# ap.net
KiCad netlist of a schematic drawn in EAGLE
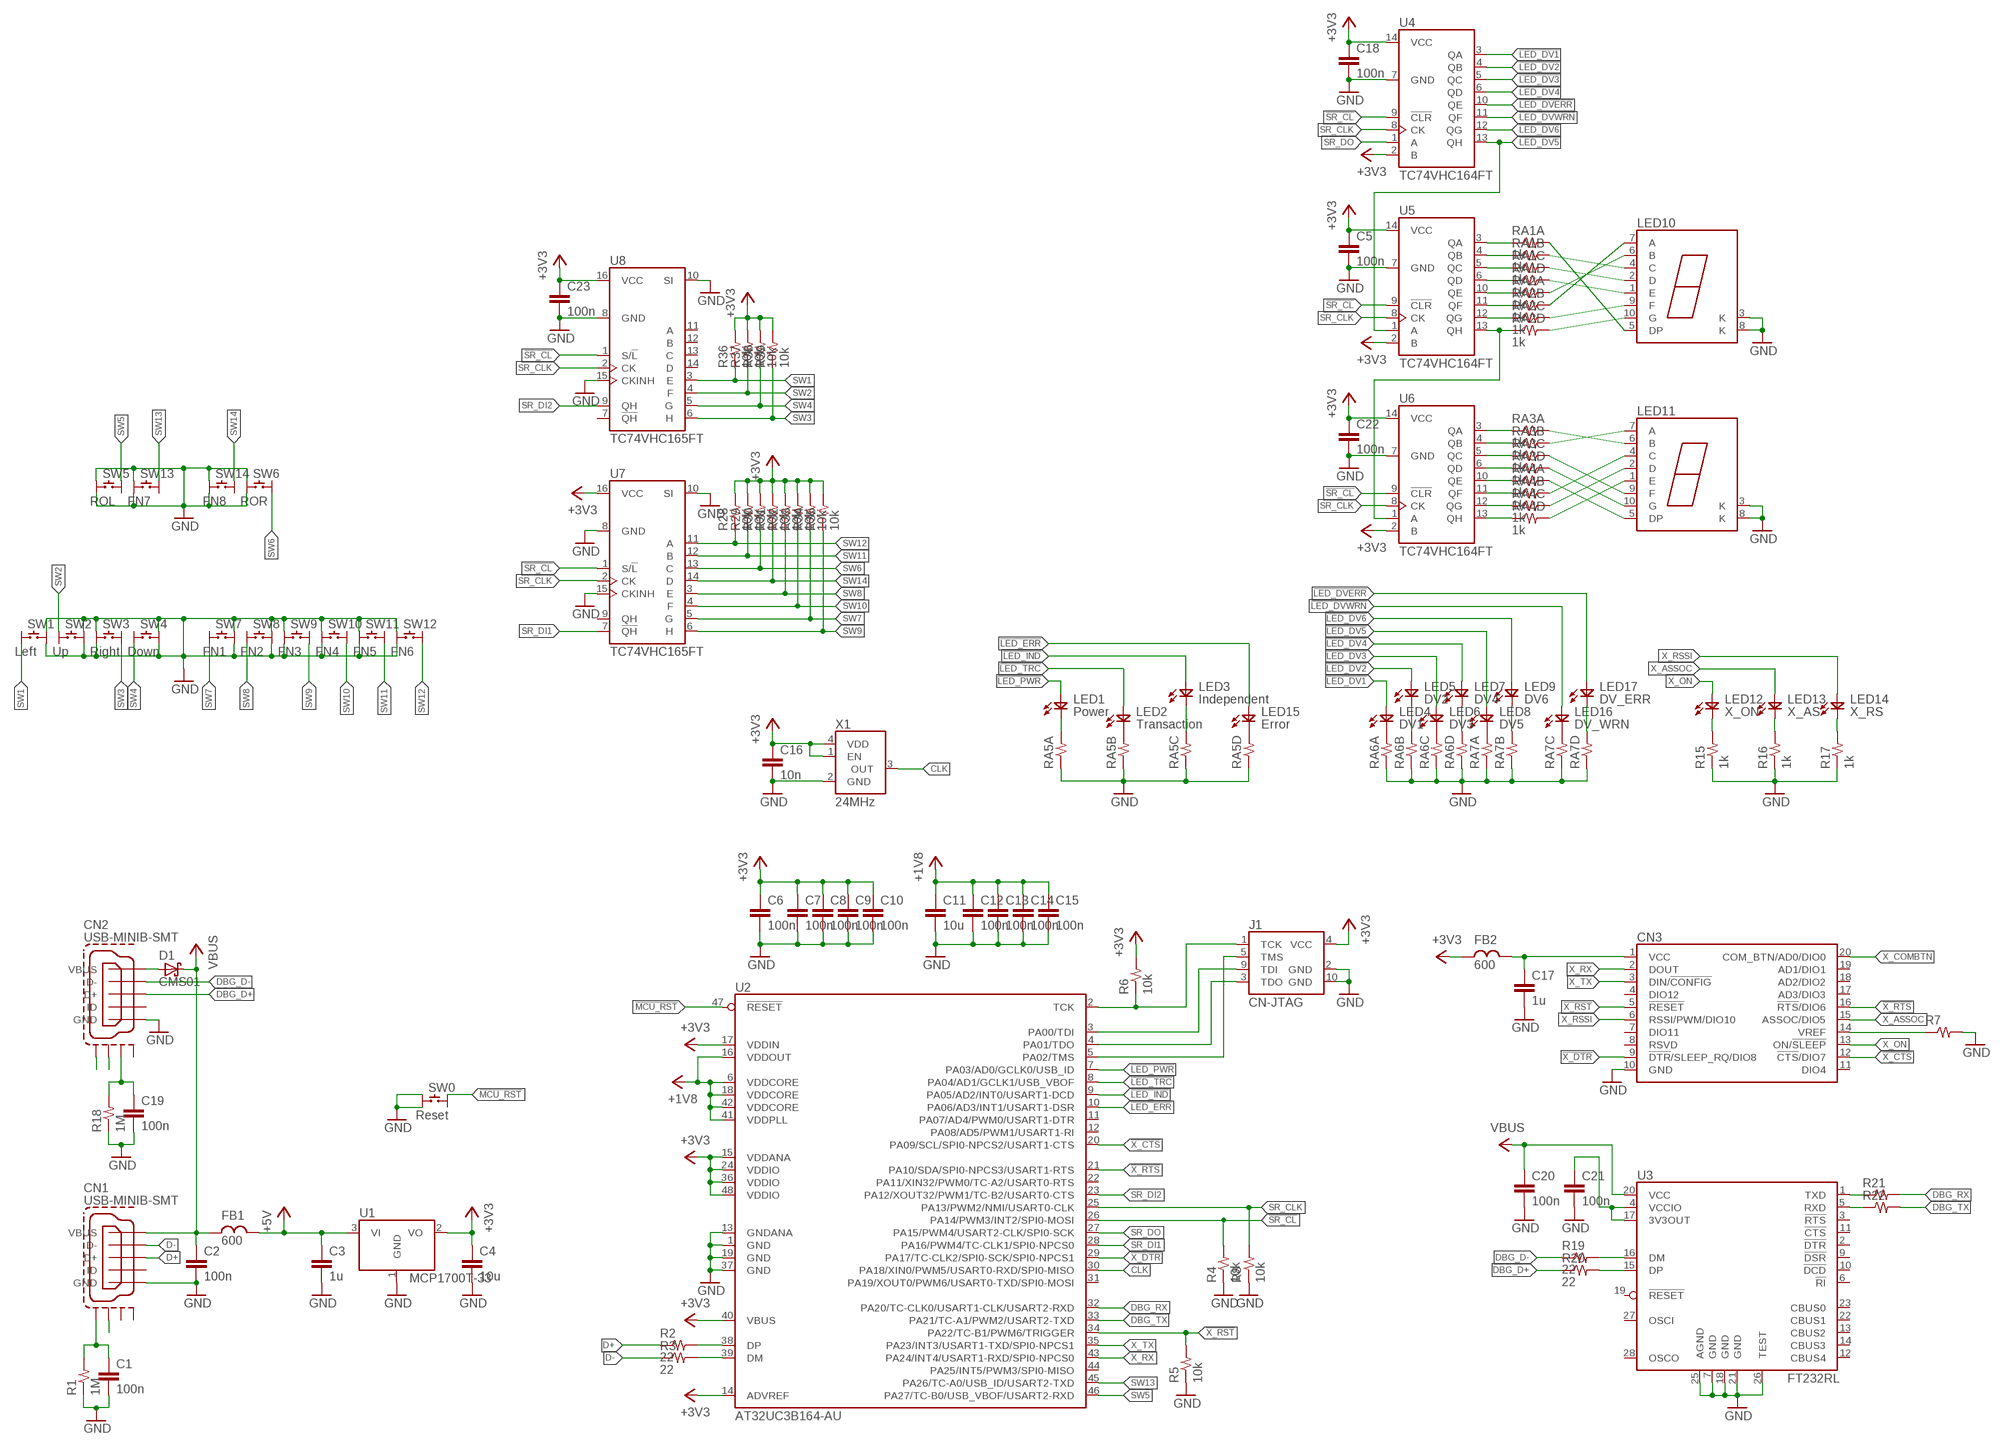
[diagram p0: schematic, sheet 1]

(export (version "E")
  (design (tool "Eeschema 10.0.6"))
  (components
    (comp (ref "C1")
      (value "100n")
      (footprint "eagle-import:1608")
      (libsource (lib "eagle-import") (part "C1608"))
    )
    (comp (ref "C2")
      (value "100n")
      (footprint "eagle-import:1608")
      (libsource (lib "eagle-import") (part "C1608"))
    )
    (comp (ref "C3")
      (value "1u")
      (footprint "eagle-import:1608")
      (libsource (lib "eagle-import") (part "C1608"))
    )
    (comp (ref "C4")
      (value "10u")
      (footprint "eagle-import:2012")
      (libsource (lib "eagle-import") (part "C2012"))
    )
    (comp (ref "C5")
      (value "100n")
      (footprint "eagle-import:1005")
      (libsource (lib "eagle-import") (part "C1005"))
    )
    (comp (ref "C6")
      (value "100n")
      (footprint "eagle-import:1005")
      (libsource (lib "eagle-import") (part "C1005"))
    )
    (comp (ref "C7")
      (value "100n")
      (footprint "eagle-import:1005")
      (libsource (lib "eagle-import") (part "C1005"))
    )
    (comp (ref "C8")
      (value "100n")
      (footprint "eagle-import:1005")
      (libsource (lib "eagle-import") (part "C1005"))
    )
    (comp (ref "C9")
      (value "100n")
      (footprint "eagle-import:1005")
      (libsource (lib "eagle-import") (part "C1005"))
    )
    (comp (ref "C10")
      (value "100n")
      (footprint "eagle-import:1005")
      (libsource (lib "eagle-import") (part "C1005"))
    )
    (comp (ref "C11")
      (value "10u")
      (footprint "eagle-import:2012")
      (libsource (lib "eagle-import") (part "C2012"))
    )
    (comp (ref "C12")
      (value "100n")
      (footprint "eagle-import:1005")
      (libsource (lib "eagle-import") (part "C1005"))
    )
    (comp (ref "C13")
      (value "100n")
      (footprint "eagle-import:1005")
      (libsource (lib "eagle-import") (part "C1005"))
    )
    (comp (ref "C14")
      (value "100n")
      (footprint "eagle-import:1005")
      (libsource (lib "eagle-import") (part "C1005"))
    )
    (comp (ref "C15")
      (value "100n")
      (footprint "eagle-import:1005")
      (libsource (lib "eagle-import") (part "C1005"))
    )
    (comp (ref "C16")
      (value "10n")
      (footprint "eagle-import:1005")
      (libsource (lib "eagle-import") (part "C1005"))
    )
    (comp (ref "C17")
      (value "1u")
      (footprint "eagle-import:1608")
      (libsource (lib "eagle-import") (part "C1608"))
    )
    (comp (ref "C18")
      (value "100n")
      (footprint "eagle-import:1005")
      (libsource (lib "eagle-import") (part "C1005"))
    )
    (comp (ref "C19")
      (value "100n")
      (footprint "eagle-import:1608")
      (libsource (lib "eagle-import") (part "C1608"))
    )
    (comp (ref "C20")
      (value "100n")
      (footprint "eagle-import:1608")
      (libsource (lib "eagle-import") (part "C1608"))
    )
    (comp (ref "C21")
      (value "100n")
      (footprint "eagle-import:1608")
      (libsource (lib "eagle-import") (part "C1608"))
    )
    (comp (ref "C22")
      (value "100n")
      (footprint "eagle-import:1005")
      (libsource (lib "eagle-import") (part "C1005"))
    )
    (comp (ref "C23")
      (value "100n")
      (footprint "eagle-import:1005")
      (libsource (lib "eagle-import") (part "C1005"))
    )
    (comp (ref "CN1")
      (value "USB-MINIB-SMT")
      (footprint "eagle-import:USB-MINIB-SMT")
      (libsource (lib "eagle-import") (part "USB-MINIB-SMT"))
    )
    (comp (ref "CN2")
      (value "USB-MINIB-SMT")
      (footprint "eagle-import:USB-MINIB-SMT")
      (libsource (lib "eagle-import") (part "USB-MINIB-SMT"))
    )
    (comp (ref "CN3")
      (value "XBEE-SMT")
      (footprint "eagle-import:XBEE-SMT")
      (libsource (lib "eagle-import") (part "XBEE-SMT"))
    )
    (comp (ref "D1")
      (value "CMS01")
      (footprint "eagle-import:3-4E1A")
      (libsource (lib "eagle-import") (part "CMS01"))
    )
    (comp (ref "FB1")
      (value "600")
      (footprint "eagle-import:1608")
      (libsource (lib "eagle-import") (part "FB1608"))
    )
    (comp (ref "FB2")
      (value "600")
      (footprint "eagle-import:1608")
      (libsource (lib "eagle-import") (part "FB1608"))
    )
    (comp (ref "J1")
      (value "CN-JTAG")
      (footprint "eagle-import:PIN2X5")
      (libsource (lib "eagle-import") (part "CN-JTAG_ALTERA"))
    )
    (comp (ref "LED1")
      (value "Power")
      (footprint "eagle-import:LED1608")
      (libsource (lib "eagle-import") (part "LED1608"))
    )
    (comp (ref "LED2")
      (value "Transaction")
      (footprint "eagle-import:LED1608")
      (libsource (lib "eagle-import") (part "LED1608"))
    )
    (comp (ref "LED3")
      (value "Independent")
      (footprint "eagle-import:LED1608")
      (libsource (lib "eagle-import") (part "LED1608"))
    )
    (comp (ref "LED4")
      (value "DV1")
      (footprint "eagle-import:LED1608")
      (libsource (lib "eagle-import") (part "LED1608"))
    )
    (comp (ref "LED5")
      (value "DV2")
      (footprint "eagle-import:LED1608")
      (libsource (lib "eagle-import") (part "LED1608"))
    )
    (comp (ref "LED6")
      (value "DV3")
      (footprint "eagle-import:LED1608")
      (libsource (lib "eagle-import") (part "LED1608"))
    )
    (comp (ref "LED7")
      (value "DV4")
      (footprint "eagle-import:LED1608")
      (libsource (lib "eagle-import") (part "LED1608"))
    )
    (comp (ref "LED8")
      (value "DV5")
      (footprint "eagle-import:LED1608")
      (libsource (lib "eagle-import") (part "LED1608"))
    )
    (comp (ref "LED9")
      (value "DV6")
      (footprint "eagle-import:LED1608")
      (libsource (lib "eagle-import") (part "LED1608"))
    )
    (comp (ref "LED10")
      (value "ACSC02")
      (footprint "eagle-import:ACSC02")
      (libsource (lib "eagle-import") (part "ACSC02"))
    )
    (comp (ref "LED11")
      (value "ACSC02")
      (footprint "eagle-import:ACSC02")
      (libsource (lib "eagle-import") (part "ACSC02"))
    )
    (comp (ref "LED12")
      (value "X_ON")
      (footprint "eagle-import:LED1608")
      (libsource (lib "eagle-import") (part "LED1608"))
    )
    (comp (ref "LED13")
      (value "X_AS")
      (footprint "eagle-import:LED1608")
      (libsource (lib "eagle-import") (part "LED1608"))
    )
    (comp (ref "LED14")
      (value "X_RS")
      (footprint "eagle-import:LED1608")
      (libsource (lib "eagle-import") (part "LED1608"))
    )
    (comp (ref "LED15")
      (value "Error")
      (footprint "eagle-import:LED1608")
      (libsource (lib "eagle-import") (part "LED1608"))
    )
    (comp (ref "LED16")
      (value "DV_WRN")
      (footprint "eagle-import:LED1608")
      (libsource (lib "eagle-import") (part "LED1608"))
    )
    (comp (ref "LED17")
      (value "DV_ERR")
      (footprint "eagle-import:LED1608")
      (libsource (lib "eagle-import") (part "LED1608"))
    )
    (comp (ref "R1")
      (value "1M")
      (footprint "eagle-import:1608")
      (libsource (lib "eagle-import") (part "R1608"))
    )
    (comp (ref "R2")
      (value "22")
      (footprint "eagle-import:1608")
      (libsource (lib "eagle-import") (part "R1608"))
    )
    (comp (ref "R3")
      (value "22")
      (footprint "eagle-import:1608")
      (libsource (lib "eagle-import") (part "R1608"))
    )
    (comp (ref "R4")
      (value "10k")
      (footprint "eagle-import:1005")
      (libsource (lib "eagle-import") (part "R1005"))
    )
    (comp (ref "R5")
      (value "10k")
      (footprint "eagle-import:1005")
      (libsource (lib "eagle-import") (part "R1005"))
    )
    (comp (ref "R6")
      (value "10k")
      (footprint "eagle-import:1005")
      (libsource (lib "eagle-import") (part "R1005"))
    )
    (comp (ref "R7")
      (value "R1608")
      (footprint "eagle-import:1608")
      (libsource (lib "eagle-import") (part "R1608"))
    )
    (comp (ref "R8")
      (value "10k")
      (footprint "eagle-import:1005")
      (libsource (lib "eagle-import") (part "R1005"))
    )
    (comp (ref "R15")
      (value "1k")
      (footprint "eagle-import:1608")
      (libsource (lib "eagle-import") (part "R1608"))
    )
    (comp (ref "R16")
      (value "1k")
      (footprint "eagle-import:1608")
      (libsource (lib "eagle-import") (part "R1608"))
    )
    (comp (ref "R17")
      (value "1k")
      (footprint "eagle-import:1608")
      (libsource (lib "eagle-import") (part "R1608"))
    )
    (comp (ref "R18")
      (value "1M")
      (footprint "eagle-import:1608")
      (libsource (lib "eagle-import") (part "R1608"))
    )
    (comp (ref "R19")
      (value "22")
      (footprint "eagle-import:1608")
      (libsource (lib "eagle-import") (part "R1608"))
    )
    (comp (ref "R20")
      (value "22")
      (footprint "eagle-import:1608")
      (libsource (lib "eagle-import") (part "R1608"))
    )
    (comp (ref "R21")
      (value "R1608")
      (footprint "eagle-import:1608")
      (libsource (lib "eagle-import") (part "R1608"))
    )
    (comp (ref "R22")
      (value "R1608")
      (footprint "eagle-import:1608")
      (libsource (lib "eagle-import") (part "R1608"))
    )
    (comp (ref "R28")
      (value "10k")
      (footprint "eagle-import:1005")
      (libsource (lib "eagle-import") (part "R1005"))
    )
    (comp (ref "R29")
      (value "10k")
      (footprint "eagle-import:1005")
      (libsource (lib "eagle-import") (part "R1005"))
    )
    (comp (ref "R30")
      (value "10k")
      (footprint "eagle-import:1005")
      (libsource (lib "eagle-import") (part "R1005"))
    )
    (comp (ref "R31")
      (value "10k")
      (footprint "eagle-import:1005")
      (libsource (lib "eagle-import") (part "R1005"))
    )
    (comp (ref "R32")
      (value "10k")
      (footprint "eagle-import:1005")
      (libsource (lib "eagle-import") (part "R1005"))
    )
    (comp (ref "R33")
      (value "10k")
      (footprint "eagle-import:1005")
      (libsource (lib "eagle-import") (part "R1005"))
    )
    (comp (ref "R34")
      (value "10k")
      (footprint "eagle-import:1005")
      (libsource (lib "eagle-import") (part "R1005"))
    )
    (comp (ref "R35")
      (value "10k")
      (footprint "eagle-import:1005")
      (libsource (lib "eagle-import") (part "R1005"))
    )
    (comp (ref "R36")
      (value "10k")
      (footprint "eagle-import:1005")
      (libsource (lib "eagle-import") (part "R1005"))
    )
    (comp (ref "R37")
      (value "10k")
      (footprint "eagle-import:1005")
      (libsource (lib "eagle-import") (part "R1005"))
    )
    (comp (ref "R38")
      (value "10k")
      (footprint "eagle-import:1005")
      (libsource (lib "eagle-import") (part "R1005"))
    )
    (comp (ref "R39")
      (value "10k")
      (footprint "eagle-import:1005")
      (libsource (lib "eagle-import") (part "R1005"))
    )
    (comp (ref "RA1")
      (value "1k")
      (footprint "eagle-import:1005-A4")
      (libsource (lib "eagle-import") (part "RA4"))
    )
    (comp (ref "RA2")
      (value "1k")
      (footprint "eagle-import:1005-A4")
      (libsource (lib "eagle-import") (part "RA4"))
    )
    (comp (ref "RA3")
      (value "1k")
      (footprint "eagle-import:1005-A4")
      (libsource (lib "eagle-import") (part "RA4"))
    )
    (comp (ref "RA4")
      (value "1k")
      (footprint "eagle-import:1005-A4")
      (libsource (lib "eagle-import") (part "RA4"))
    )
    (comp (ref "RA5")
      (value "RA4")
      (footprint "eagle-import:1005-A4")
      (libsource (lib "eagle-import") (part "RA4"))
    )
    (comp (ref "RA6")
      (value "RA4")
      (footprint "eagle-import:1005-A4")
      (libsource (lib "eagle-import") (part "RA4"))
    )
    (comp (ref "RA7")
      (value "RA4")
      (footprint "eagle-import:1005-A4")
      (libsource (lib "eagle-import") (part "RA4"))
    )
    (comp (ref "SW0")
      (value "Reset")
      (footprint "eagle-import:TACT4P-SMT6660")
      (libsource (lib "eagle-import") (part "TACT4P-SMT6660"))
    )
    (comp (ref "SW1")
      (value "Left")
      (footprint "eagle-import:TACT4P-SMT-6660")
      (libsource (lib "eagle-import") (part "TACT4P-SMT-6660"))
    )
    (comp (ref "SW2")
      (value "Up")
      (footprint "eagle-import:TACT4P-SMT-6660")
      (libsource (lib "eagle-import") (part "TACT4P-SMT-6660"))
    )
    (comp (ref "SW3")
      (value "Right")
      (footprint "eagle-import:TACT4P-SMT-6660")
      (libsource (lib "eagle-import") (part "TACT4P-SMT-6660"))
    )
    (comp (ref "SW4")
      (value "Down")
      (footprint "eagle-import:TACT4P-SMT-6660")
      (libsource (lib "eagle-import") (part "TACT4P-SMT-6660"))
    )
    (comp (ref "SW5")
      (value "ROL")
      (footprint "eagle-import:TACT4P-SMT-4735R")
      (libsource (lib "eagle-import") (part "TACT4P-SMT-4735R"))
    )
    (comp (ref "SW6")
      (value "ROR")
      (footprint "eagle-import:TACT4P-SMT-4735R")
      (libsource (lib "eagle-import") (part "TACT4P-SMT-4735R"))
    )
    (comp (ref "SW7")
      (value "FN1")
      (footprint "eagle-import:TACT4P-SMT-6660")
      (libsource (lib "eagle-import") (part "TACT4P-SMT-6660"))
    )
    (comp (ref "SW8")
      (value "FN2")
      (footprint "eagle-import:TACT4P-SMT-6660")
      (libsource (lib "eagle-import") (part "TACT4P-SMT-6660"))
    )
    (comp (ref "SW9")
      (value "FN3")
      (footprint "eagle-import:TACT4P-SMT-6660")
      (libsource (lib "eagle-import") (part "TACT4P-SMT-6660"))
    )
    (comp (ref "SW10")
      (value "FN4")
      (footprint "eagle-import:TACT4P-SMT-6660")
      (libsource (lib "eagle-import") (part "TACT4P-SMT-6660"))
    )
    (comp (ref "SW11")
      (value "FN5")
      (footprint "eagle-import:TACT4P-SMT-6660")
      (libsource (lib "eagle-import") (part "TACT4P-SMT-6660"))
    )
    (comp (ref "SW12")
      (value "FN6")
      (footprint "eagle-import:TACT4P-SMT-6660")
      (libsource (lib "eagle-import") (part "TACT4P-SMT-6660"))
    )
    (comp (ref "SW13")
      (value "FN7")
      (footprint "eagle-import:TACT4P-SMT-4735R")
      (libsource (lib "eagle-import") (part "TACT4P-SMT-4735R"))
    )
    (comp (ref "SW14")
      (value "FN8")
      (footprint "eagle-import:TACT4P-SMT-4735R")
      (libsource (lib "eagle-import") (part "TACT4P-SMT-4735R"))
    )
    (comp (ref "U1")
      (value "MCP1700T-33")
      (footprint "eagle-import:SOT23-3")
      (libsource (lib "eagle-import") (part "MCP1700T-33"))
    )
    (comp (ref "U2")
      (value "AT32UC3B164-AU")
      (footprint "eagle-import:QFP48-0.5")
      (libsource (lib "eagle-import") (part "AT32UC3B1-AU64"))
    )
    (comp (ref "U3")
      (value "FT232RL")
      (footprint "eagle-import:SSOP28")
      (libsource (lib "eagle-import") (part "FT232RL"))
    )
    (comp (ref "U4")
      (value "TC74VHC164FT")
      (footprint "eagle-import:TSSOP14")
      (libsource (lib "eagle-import") (part "TC74VHC164FT"))
    )
    (comp (ref "U5")
      (value "TC74VHC164FT")
      (footprint "eagle-import:TSSOP14")
      (libsource (lib "eagle-import") (part "TC74VHC164FT"))
    )
    (comp (ref "U6")
      (value "TC74VHC164FT")
      (footprint "eagle-import:TSSOP14")
      (libsource (lib "eagle-import") (part "TC74VHC164FT"))
    )
    (comp (ref "U7")
      (value "TC74VHC165FT")
      (footprint "eagle-import:TSSOP16")
      (libsource (lib "eagle-import") (part "TC74VHC165FT"))
    )
    (comp (ref "U8")
      (value "TC74VHC165FT")
      (footprint "eagle-import:TSSOP16")
      (libsource (lib "eagle-import") (part "TC74VHC165FT"))
    )
    (comp (ref "X1")
      (value "24MHz")
      (footprint "eagle-import:OSC2520")
      (libsource (lib "eagle-import") (part "ASDM"))
    )
  )
  (nets
    (net (code "1") (name "+1V8") (class "Default")
      (node (ref "C11") (pin "1") (pinfunction "1_1") (pintype "passive"))
      (node (ref "C12") (pin "1") (pinfunction "1_1") (pintype "passive"))
      (node (ref "C13") (pin "1") (pinfunction "1_1") (pintype "passive"))
      (node (ref "C14") (pin "1") (pinfunction "1_1") (pintype "passive"))
      (node (ref "C15") (pin "1") (pinfunction "1_1") (pintype "passive"))
      (node (ref "U2") (pin "16") (pinfunction "VDDOUT_16") (pintype "bidirectional"))
      (node (ref "U2") (pin "18") (pinfunction "VDDCORE_18") (pintype "bidirectional"))
      (node (ref "U2") (pin "41") (pinfunction "VDDPLL_41") (pintype "bidirectional"))
      (node (ref "U2") (pin "42") (pinfunction "VDDCORE_42") (pintype "bidirectional"))
      (node (ref "U2") (pin "6") (pinfunction "VDDCORE_6") (pintype "bidirectional"))
    )
    (net (code "2") (name "+3V3") (class "Default")
      (node (ref "C10") (pin "1") (pinfunction "1_1") (pintype "passive"))
      (node (ref "C16") (pin "1") (pinfunction "1_1") (pintype "passive"))
      (node (ref "C18") (pin "1") (pinfunction "1_1") (pintype "passive"))
      (node (ref "C22") (pin "1") (pinfunction "1_1") (pintype "passive"))
      (node (ref "C23") (pin "1") (pinfunction "1_1") (pintype "passive"))
      (node (ref "C4") (pin "1") (pinfunction "1_1") (pintype "passive"))
      (node (ref "C5") (pin "1") (pinfunction "1_1") (pintype "passive"))
      (node (ref "C6") (pin "1") (pinfunction "1_1") (pintype "passive"))
      (node (ref "C7") (pin "1") (pinfunction "1_1") (pintype "passive"))
      (node (ref "C8") (pin "1") (pinfunction "1_1") (pintype "passive"))
      (node (ref "C9") (pin "1") (pinfunction "1_1") (pintype "passive"))
      (node (ref "FB2") (pin "1") (pinfunction "1_1") (pintype "passive"))
      (node (ref "J1") (pin "4") (pinfunction "VCC_4") (pintype "passive"))
      (node (ref "R28") (pin "2") (pinfunction "2_2") (pintype "passive"))
      (node (ref "R29") (pin "2") (pinfunction "2_2") (pintype "passive"))
      (node (ref "R30") (pin "2") (pinfunction "2_2") (pintype "passive"))
      (node (ref "R31") (pin "2") (pinfunction "2_2") (pintype "passive"))
      (node (ref "R32") (pin "2") (pinfunction "2_2") (pintype "passive"))
      (node (ref "R33") (pin "2") (pinfunction "2_2") (pintype "passive"))
      (node (ref "R34") (pin "2") (pinfunction "2_2") (pintype "passive"))
      (node (ref "R35") (pin "2") (pinfunction "2_2") (pintype "passive"))
      (node (ref "R36") (pin "2") (pinfunction "2_2") (pintype "passive"))
      (node (ref "R37") (pin "2") (pinfunction "2_2") (pintype "passive"))
      (node (ref "R38") (pin "2") (pinfunction "2_2") (pintype "passive"))
      (node (ref "R39") (pin "2") (pinfunction "2_2") (pintype "passive"))
      (node (ref "R6") (pin "2") (pinfunction "2_2") (pintype "passive"))
      (node (ref "U1") (pin "2") (pinfunction "VO_2") (pintype "bidirectional"))
      (node (ref "U2") (pin "14") (pinfunction "ADVREF_14") (pintype "bidirectional"))
      (node (ref "U2") (pin "15") (pinfunction "VDDANA_15") (pintype "bidirectional"))
      (node (ref "U2") (pin "17") (pinfunction "VDDIN_17") (pintype "bidirectional"))
      (node (ref "U2") (pin "24") (pinfunction "VDDIO_24") (pintype "bidirectional"))
      (node (ref "U2") (pin "36") (pinfunction "VDDIO_36") (pintype "bidirectional"))
      (node (ref "U2") (pin "40") (pinfunction "VBUS_40") (pintype "bidirectional"))
      (node (ref "U2") (pin "48") (pinfunction "VDDIO_48") (pintype "bidirectional"))
      (node (ref "U4") (pin "14") (pinfunction "VCC_14") (pintype "bidirectional"))
      (node (ref "U4") (pin "2") (pinfunction "B_2") (pintype "bidirectional"))
      (node (ref "U5") (pin "14") (pinfunction "VCC_14") (pintype "bidirectional"))
      (node (ref "U5") (pin "2") (pinfunction "B_2") (pintype "bidirectional"))
      (node (ref "U6") (pin "14") (pinfunction "VCC_14") (pintype "bidirectional"))
      (node (ref "U6") (pin "2") (pinfunction "B_2") (pintype "bidirectional"))
      (node (ref "U7") (pin "16") (pinfunction "VCC_16") (pintype "bidirectional"))
      (node (ref "U8") (pin "16") (pinfunction "VCC_16") (pintype "bidirectional"))
      (node (ref "X1") (pin "1") (pinfunction "EN_1") (pintype "bidirectional"))
      (node (ref "X1") (pin "4") (pinfunction "VDD_4") (pintype "bidirectional"))
    )
    (net (code "3") (name "+5V") (class "Default")
      (node (ref "C3") (pin "1") (pinfunction "1_1") (pintype "passive"))
      (node (ref "FB1") (pin "2") (pinfunction "2_2") (pintype "passive"))
      (node (ref "U1") (pin "3") (pinfunction "VI_3") (pintype "bidirectional"))
    )
    (net (code "4") (name "/~{LED_DV1}") (class "Default")
      (node (ref "LED4") (pin "A") (pinfunction "A_A") (pintype "passive"))
      (node (ref "U4") (pin "3") (pinfunction "QA_3") (pintype "bidirectional"))
    )
    (net (code "5") (name "/~{LED_DV2}") (class "Default")
      (node (ref "LED5") (pin "A") (pinfunction "A_A") (pintype "passive"))
      (node (ref "U4") (pin "4") (pinfunction "QB_4") (pintype "bidirectional"))
    )
    (net (code "6") (name "/~{LED_DV3}") (class "Default")
      (node (ref "LED6") (pin "A") (pinfunction "A_A") (pintype "passive"))
      (node (ref "U4") (pin "5") (pinfunction "QC_5") (pintype "bidirectional"))
    )
    (net (code "7") (name "/~{LED_DV4}") (class "Default")
      (node (ref "LED7") (pin "A") (pinfunction "A_A") (pintype "passive"))
      (node (ref "U4") (pin "6") (pinfunction "QD_6") (pintype "bidirectional"))
    )
    (net (code "8") (name "/~{LED_DV5}") (class "Default")
      (node (ref "LED8") (pin "A") (pinfunction "A_A") (pintype "passive"))
      (node (ref "U4") (pin "13") (pinfunction "QH_13") (pintype "bidirectional"))
      (node (ref "U5") (pin "1") (pinfunction "A_1") (pintype "bidirectional"))
    )
    (net (code "9") (name "/~{LED_DV6}") (class "Default")
      (node (ref "LED9") (pin "A") (pinfunction "A_A") (pintype "passive"))
      (node (ref "U4") (pin "12") (pinfunction "QG_12") (pintype "bidirectional"))
    )
    (net (code "10") (name "/~{LED_DVERR}") (class "Default")
      (node (ref "LED17") (pin "A") (pinfunction "A_A") (pintype "passive"))
      (node (ref "U4") (pin "10") (pinfunction "QE_10") (pintype "bidirectional"))
    )
    (net (code "11") (name "/~{LED_DVWRN}") (class "Default")
      (node (ref "LED16") (pin "A") (pinfunction "A_A") (pintype "passive"))
      (node (ref "U4") (pin "11") (pinfunction "QF_11") (pintype "bidirectional"))
    )
    (net (code "12") (name "/~{LED_ERR}") (class "Default")
      (node (ref "LED15") (pin "A") (pinfunction "A_A") (pintype "passive"))
      (node (ref "U2") (pin "10") (pinfunction "PA06/AD3/INT1/USART1-DSR_10") (pintype "bidirectional"))
    )
    (net (code "13") (name "/~{LED_IND}") (class "Default")
      (node (ref "LED3") (pin "A") (pinfunction "A_A") (pintype "passive"))
      (node (ref "U2") (pin "9") (pinfunction "PA05/AD2/INT0/USART1-DCD_9") (pintype "bidirectional"))
    )
    (net (code "14") (name "/~{LED_PWR}") (class "Default")
      (node (ref "LED1") (pin "A") (pinfunction "A_A") (pintype "passive"))
      (node (ref "U2") (pin "7") (pinfunction "PA03/AD0/GCLK0/USB_ID_7") (pintype "bidirectional"))
    )
    (net (code "15") (name "/~{LED_TRC}") (class "Default")
      (node (ref "LED2") (pin "A") (pinfunction "A_A") (pintype "passive"))
      (node (ref "U2") (pin "8") (pinfunction "PA04/AD1/GCLK1/USB_VBOF_8") (pintype "bidirectional"))
    )
    (net (code "16") (name "/~{MCU_RST}") (class "Default")
      (node (ref "SW0") (pin "B1") (pinfunction "B1_B1") (pintype "passive"))
      (node (ref "U2") (pin "47") (pinfunction "~{RESET}_47") (pintype "bidirectional"))
    )
    (net (code "17") (name "/~{SR_CL}") (class "Default")
      (node (ref "R4") (pin "2") (pinfunction "2_2") (pintype "passive"))
      (node (ref "U2") (pin "26") (pinfunction "PA14/PWM3/INT2/SPI0-MOSI_26") (pintype "bidirectional"))
      (node (ref "U4") (pin "9") (pinfunction "~{CLR}_9") (pintype "bidirectional"))
      (node (ref "U5") (pin "9") (pinfunction "~{CLR}_9") (pintype "bidirectional"))
      (node (ref "U6") (pin "9") (pinfunction "~{CLR}_9") (pintype "bidirectional"))
      (node (ref "U7") (pin "1") (pinfunction "S/~{L}_1") (pintype "bidirectional"))
      (node (ref "U8") (pin "1") (pinfunction "S/~{L}_1") (pintype "bidirectional"))
    )
    (net (code "18") (name "/~{X_CTS}") (class "Default")
      (node (ref "CN3") (pin "12") (pinfunction "~{CTS}/DIO7_12") (pintype "bidirectional"))
      (node (ref "U2") (pin "20") (pinfunction "PA09/SCL/SPI0-NPCS2/USART1-CTS_20") (pintype "bidirectional"))
    )
    (net (code "19") (name "/~{X_DTR}") (class "Default")
      (node (ref "CN3") (pin "9") (pinfunction "~{DTR}/SLEEP_RQ/DIO8_9") (pintype "bidirectional"))
      (node (ref "U2") (pin "29") (pinfunction "PA17/TC-CLK2/SPI0-SCK/SPI0-NPCS1_29") (pintype "bidirectional"))
    )
    (net (code "20") (name "/~{X_RST}") (class "Default")
      (node (ref "CN3") (pin "5") (pinfunction "~{RESET}_5") (pintype "bidirectional"))
      (node (ref "R5") (pin "2") (pinfunction "2_2") (pintype "passive"))
      (node (ref "U2") (pin "34") (pinfunction "PA22/TC-B1/PWM6/TRIGGER_34") (pintype "bidirectional"))
    )
    (net (code "21") (name "/~{X_RTS}") (class "Default")
      (node (ref "CN3") (pin "16") (pinfunction "~{RTS}/DIO6_16") (pintype "bidirectional"))
      (node (ref "U2") (pin "21") (pinfunction "PA10/SDA/SPI0-NPCS3/USART1-RTS_21") (pintype "bidirectional"))
    )
    (net (code "22") (name "CLK") (class "Default")
      (node (ref "U2") (pin "30") (pinfunction "PA18/XIN0/PWM5/USART0-RXD/SPI0-MISO_30") (pintype "bidirectional"))
      (node (ref "X1") (pin "3") (pinfunction "OUT_3") (pintype "bidirectional"))
    )
    (net (code "23") (name "D+") (class "Default")
      (node (ref "CN1") (pin "3") (pinfunction "D+_3") (pintype "passive"))
      (node (ref "R2") (pin "1") (pinfunction "1_1") (pintype "passive"))
    )
    (net (code "24") (name "D-") (class "Default")
      (node (ref "CN1") (pin "2") (pinfunction "D-_2") (pintype "passive"))
      (node (ref "R3") (pin "1") (pinfunction "1_1") (pintype "passive"))
    )
    (net (code "25") (name "DBG_D+") (class "Default")
      (node (ref "CN2") (pin "3") (pinfunction "D+_3") (pintype "passive"))
      (node (ref "R20") (pin "1") (pinfunction "1_1") (pintype "passive"))
    )
    (net (code "26") (name "DBG_D-") (class "Default")
      (node (ref "CN2") (pin "2") (pinfunction "D-_2") (pintype "passive"))
      (node (ref "R19") (pin "1") (pinfunction "1_1") (pintype "passive"))
    )
    (net (code "27") (name "DBG_RX") (class "Default")
      (node (ref "R21") (pin "2") (pinfunction "2_2") (pintype "passive"))
      (node (ref "U2") (pin "32") (pinfunction "PA20/TC-CLK0/USART1-CLK/USART2-RXD_32") (pintype "bidirectional"))
    )
    (net (code "28") (name "DBG_TX") (class "Default")
      (node (ref "R22") (pin "2") (pinfunction "2_2") (pintype "passive"))
      (node (ref "U2") (pin "33") (pinfunction "PA21/TC-A1/PWM2/USART2-TXD_33") (pintype "bidirectional"))
    )
    (net (code "29") (name "GND") (class "Default")
      (node (ref "C1") (pin "2") (pinfunction "2_2") (pintype "passive"))
      (node (ref "C10") (pin "2") (pinfunction "2_2") (pintype "passive"))
      (node (ref "C11") (pin "2") (pinfunction "2_2") (pintype "passive"))
      (node (ref "C12") (pin "2") (pinfunction "2_2") (pintype "passive"))
      (node (ref "C13") (pin "2") (pinfunction "2_2") (pintype "passive"))
      (node (ref "C14") (pin "2") (pinfunction "2_2") (pintype "passive"))
      (node (ref "C15") (pin "2") (pinfunction "2_2") (pintype "passive"))
      (node (ref "C16") (pin "2") (pinfunction "2_2") (pintype "passive"))
      (node (ref "C17") (pin "2") (pinfunction "2_2") (pintype "passive"))
      (node (ref "C18") (pin "2") (pinfunction "2_2") (pintype "passive"))
      (node (ref "C19") (pin "2") (pinfunction "2_2") (pintype "passive"))
      (node (ref "C2") (pin "2") (pinfunction "2_2") (pintype "passive"))
      (node (ref "C20") (pin "2") (pinfunction "2_2") (pintype "passive"))
      (node (ref "C21") (pin "2") (pinfunction "2_2") (pintype "passive"))
      (node (ref "C22") (pin "2") (pinfunction "2_2") (pintype "passive"))
      (node (ref "C23") (pin "2") (pinfunction "2_2") (pintype "passive"))
      (node (ref "C3") (pin "2") (pinfunction "2_2") (pintype "passive"))
      (node (ref "C4") (pin "2") (pinfunction "2_2") (pintype "passive"))
      (node (ref "C5") (pin "2") (pinfunction "2_2") (pintype "passive"))
      (node (ref "C6") (pin "2") (pinfunction "2_2") (pintype "passive"))
      (node (ref "C7") (pin "2") (pinfunction "2_2") (pintype "passive"))
      (node (ref "C8") (pin "2") (pinfunction "2_2") (pintype "passive"))
      (node (ref "C9") (pin "2") (pinfunction "2_2") (pintype "passive"))
      (node (ref "CN1") (pin "5") (pinfunction "GND_5") (pintype "passive"))
      (node (ref "CN2") (pin "5") (pinfunction "GND_5") (pintype "passive"))
      (node (ref "CN3") (pin "10") (pinfunction "GND_10") (pintype "bidirectional"))
      (node (ref "J1") (pin "10") (pinfunction "GND_10") (pintype "passive"))
      (node (ref "J1") (pin "2") (pinfunction "GND_2") (pintype "passive"))
      (node (ref "LED10") (pin "3") (pinfunction "K_3") (pintype "bidirectional"))
      (node (ref "LED10") (pin "8") (pinfunction "K_8") (pintype "bidirectional"))
      (node (ref "LED11") (pin "3") (pinfunction "K_3") (pintype "bidirectional"))
      (node (ref "LED11") (pin "8") (pinfunction "K_8") (pintype "bidirectional"))
      (node (ref "R1") (pin "1") (pinfunction "1_1") (pintype "passive"))
      (node (ref "R15") (pin "1") (pinfunction "1_1") (pintype "passive"))
      (node (ref "R16") (pin "1") (pinfunction "1_1") (pintype "passive"))
      (node (ref "R17") (pin "1") (pinfunction "1_1") (pintype "passive"))
      (node (ref "R18") (pin "1") (pinfunction "1_1") (pintype "passive"))
      (node (ref "R4") (pin "1") (pinfunction "1_1") (pintype "passive"))
      (node (ref "R5") (pin "1") (pinfunction "1_1") (pintype "passive"))
      (node (ref "R7") (pin "2") (pinfunction "2_2") (pintype "passive"))
      (node (ref "R8") (pin "1") (pinfunction "1_1") (pintype "passive"))
      (node (ref "RA5") (pin "A1") (pinfunction "1_A1") (pintype "passive"))
      (node (ref "RA5") (pin "B1") (pinfunction "1_B1") (pintype "passive"))
      (node (ref "RA5") (pin "C1") (pinfunction "1_C1") (pintype "passive"))
      (node (ref "RA5") (pin "D1") (pinfunction "1_D1") (pintype "passive"))
      (node (ref "RA6") (pin "A1") (pinfunction "1_A1") (pintype "passive"))
      (node (ref "RA6") (pin "B1") (pinfunction "1_B1") (pintype "passive"))
      (node (ref "RA6") (pin "C1") (pinfunction "1_C1") (pintype "passive"))
      (node (ref "RA6") (pin "D1") (pinfunction "1_D1") (pintype "passive"))
      (node (ref "RA7") (pin "A1") (pinfunction "1_A1") (pintype "passive"))
      (node (ref "RA7") (pin "B1") (pinfunction "1_B1") (pintype "passive"))
      (node (ref "RA7") (pin "C1") (pinfunction "1_C1") (pintype "passive"))
      (node (ref "RA7") (pin "D1") (pinfunction "1_D1") (pintype "passive"))
      (node (ref "SW0") (pin "A1") (pinfunction "A1_A1") (pintype "passive"))
      (node (ref "SW0") (pin "A2") (pinfunction "A2_A2") (pintype "passive"))
      (node (ref "SW1") (pin "B1") (pinfunction "B1_B1") (pintype "passive"))
      (node (ref "SW1") (pin "B2") (pinfunction "B2_B2") (pintype "passive"))
      (node (ref "SW10") (pin "A1") (pinfunction "A1_A1") (pintype "passive"))
      (node (ref "SW10") (pin "A2") (pinfunction "A2_A2") (pintype "passive"))
      (node (ref "SW11") (pin "A1") (pinfunction "A1_A1") (pintype "passive"))
      (node (ref "SW11") (pin "A2") (pinfunction "A2_A2") (pintype "passive"))
      (node (ref "SW12") (pin "A1") (pinfunction "A1_A1") (pintype "passive"))
      (node (ref "SW12") (pin "A2") (pinfunction "A2_A2") (pintype "passive"))
      (node (ref "SW13") (pin "A1") (pinfunction "A1_A1") (pintype "passive"))
      (node (ref "SW13") (pin "A2") (pinfunction "A2_A2") (pintype "passive"))
      (node (ref "SW14") (pin "A1") (pinfunction "A1_A1") (pintype "passive"))
      (node (ref "SW14") (pin "A2") (pinfunction "A2_A2") (pintype "passive"))
      (node (ref "SW2") (pin "B1") (pinfunction "B1_B1") (pintype "passive"))
      (node (ref "SW2") (pin "B2") (pinfunction "B2_B2") (pintype "passive"))
      (node (ref "SW3") (pin "A1") (pinfunction "A1_A1") (pintype "passive"))
      (node (ref "SW3") (pin "A2") (pinfunction "A2_A2") (pintype "passive"))
      (node (ref "SW4") (pin "B1") (pinfunction "B1_B1") (pintype "passive"))
      (node (ref "SW4") (pin "B2") (pinfunction "B2_B2") (pintype "passive"))
      (node (ref "SW5") (pin "A1") (pinfunction "A1_A1") (pintype "passive"))
      (node (ref "SW5") (pin "A2") (pinfunction "A2_A2") (pintype "passive"))
      (node (ref "SW6") (pin "A1") (pinfunction "A1_A1") (pintype "passive"))
      (node (ref "SW6") (pin "A2") (pinfunction "A2_A2") (pintype "passive"))
      (node (ref "SW7") (pin "B1") (pinfunction "B1_B1") (pintype "passive"))
      (node (ref "SW7") (pin "B2") (pinfunction "B2_B2") (pintype "passive"))
      (node (ref "SW8") (pin "B1") (pinfunction "B1_B1") (pintype "passive"))
      (node (ref "SW8") (pin "B2") (pinfunction "B2_B2") (pintype "passive"))
      (node (ref "SW9") (pin "A1") (pinfunction "A1_A1") (pintype "passive"))
      (node (ref "SW9") (pin "A2") (pinfunction "A2_A2") (pintype "passive"))
      (node (ref "U1") (pin "1") (pinfunction "GND_1") (pintype "bidirectional"))
      (node (ref "U2") (pin "1") (pinfunction "GND_1") (pintype "bidirectional"))
      (node (ref "U2") (pin "13") (pinfunction "GNDANA_13") (pintype "bidirectional"))
      (node (ref "U2") (pin "19") (pinfunction "GND_19") (pintype "bidirectional"))
      (node (ref "U2") (pin "37") (pinfunction "GND_37") (pintype "bidirectional"))
      (node (ref "U3") (pin "18") (pinfunction "GND_18") (pintype "bidirectional"))
      (node (ref "U3") (pin "21") (pinfunction "GND_21") (pintype "bidirectional"))
      (node (ref "U3") (pin "25") (pinfunction "AGND_25") (pintype "bidirectional"))
      (node (ref "U3") (pin "26") (pinfunction "TEST_26") (pintype "bidirectional"))
      (node (ref "U3") (pin "7") (pinfunction "GND_7") (pintype "bidirectional"))
      (node (ref "U4") (pin "7") (pinfunction "GND_7") (pintype "bidirectional"))
      (node (ref "U5") (pin "7") (pinfunction "GND_7") (pintype "bidirectional"))
      (node (ref "U6") (pin "7") (pinfunction "GND_7") (pintype "bidirectional"))
      (node (ref "U7") (pin "10") (pinfunction "SI_10") (pintype "bidirectional"))
      (node (ref "U7") (pin "15") (pinfunction "CKINH_15") (pintype "bidirectional"))
      (node (ref "U7") (pin "8") (pinfunction "GND_8") (pintype "bidirectional"))
      (node (ref "U8") (pin "10") (pinfunction "SI_10") (pintype "bidirectional"))
      (node (ref "U8") (pin "15") (pinfunction "CKINH_15") (pintype "bidirectional"))
      (node (ref "U8") (pin "8") (pinfunction "GND_8") (pintype "bidirectional"))
      (node (ref "X1") (pin "2") (pinfunction "GND_2") (pintype "bidirectional"))
    )
    (net (code "30") (name "Net-(C1-Pad1)") (class "Default")
      (node (ref "C1") (pin "1") (pinfunction "1_1") (pintype "passive"))
      (node (ref "CN1") (pin "S1") (pinfunction "S1_S1") (pintype "passive"))
      (node (ref "R1") (pin "2") (pinfunction "2_2") (pintype "passive"))
    )
    (net (code "31") (name "Net-(C19-Pad1)") (class "Default")
      (node (ref "C19") (pin "1") (pinfunction "1_1") (pintype "passive"))
      (node (ref "CN2") (pin "S3") (pinfunction "S3_S3") (pintype "passive"))
      (node (ref "R18") (pin "2") (pinfunction "2_2") (pintype "passive"))
    )
    (net (code "32") (name "Net-(CN2-VBUS)") (class "Default")
      (node (ref "CN2") (pin "1") (pinfunction "VBUS_1") (pintype "passive"))
      (node (ref "D1") (pin "A") (pinfunction "A_A") (pintype "passive"))
    )
    (net (code "33") (name "Net-(CN3-VCC)") (class "Default")
      (node (ref "C17") (pin "1") (pinfunction "1_1") (pintype "passive"))
      (node (ref "CN3") (pin "1") (pinfunction "VCC_1") (pintype "bidirectional"))
      (node (ref "FB2") (pin "2") (pinfunction "2_2") (pintype "passive"))
    )
    (net (code "34") (name "Net-(CN3-VREF)") (class "Default")
      (node (ref "CN3") (pin "14") (pinfunction "VREF_14") (pintype "bidirectional"))
      (node (ref "R7") (pin "1") (pinfunction "1_1") (pintype "passive"))
    )
    (net (code "35") (name "Net-(J1-TCK)") (class "Default")
      (node (ref "J1") (pin "1") (pinfunction "TCK_1") (pintype "passive"))
      (node (ref "R6") (pin "1") (pinfunction "1_1") (pintype "passive"))
      (node (ref "U2") (pin "2") (pinfunction "TCK_2") (pintype "bidirectional"))
    )
    (net (code "36") (name "Net-(J1-TDI)") (class "Default")
      (node (ref "J1") (pin "9") (pinfunction "TDI_9") (pintype "passive"))
      (node (ref "U2") (pin "3") (pinfunction "PA00/TDI_3") (pintype "bidirectional"))
    )
    (net (code "37") (name "Net-(J1-TDO)") (class "Default")
      (node (ref "J1") (pin "3") (pinfunction "TDO_3") (pintype "passive"))
      (node (ref "U2") (pin "4") (pinfunction "PA01/TDO_4") (pintype "bidirectional"))
    )
    (net (code "38") (name "Net-(J1-TMS)") (class "Default")
      (node (ref "J1") (pin "5") (pinfunction "TMS_5") (pintype "passive"))
      (node (ref "U2") (pin "5") (pinfunction "PA02/TMS_5") (pintype "bidirectional"))
    )
    (net (code "39") (name "Net-(LED10-A)") (class "Default")
      (node (ref "LED10") (pin "7") (pinfunction "A_7") (pintype "bidirectional"))
      (node (ref "RA2") (pin "B2") (pinfunction "2_B2") (pintype "passive"))
    )
    (net (code "40") (name "Net-(LED10-B)") (class "Default")
      (node (ref "LED10") (pin "6") (pinfunction "B_6") (pintype "bidirectional"))
      (node (ref "RA2") (pin "A2") (pinfunction "2_A2") (pintype "passive"))
    )
    (net (code "41") (name "Net-(LED10-C)") (class "Default")
      (node (ref "LED10") (pin "4") (pinfunction "C_4") (pintype "bidirectional"))
      (node (ref "RA1") (pin "B2") (pinfunction "2_B2") (pintype "passive"))
    )
    (net (code "42") (name "Net-(LED10-D)") (class "Default")
      (node (ref "LED10") (pin "2") (pinfunction "D_2") (pintype "bidirectional"))
      (node (ref "RA1") (pin "C2") (pinfunction "2_C2") (pintype "passive"))
    )
    (net (code "43") (name "Net-(LED10-DP)") (class "Default")
      (node (ref "LED10") (pin "5") (pinfunction "DP_5") (pintype "bidirectional"))
      (node (ref "RA1") (pin "A2") (pinfunction "2_A2") (pintype "passive"))
    )
    (net (code "44") (name "Net-(LED10-E)") (class "Default")
      (node (ref "LED10") (pin "1") (pinfunction "E_1") (pintype "bidirectional"))
      (node (ref "RA1") (pin "D2") (pinfunction "2_D2") (pintype "passive"))
    )
    (net (code "45") (name "Net-(LED10-F)") (class "Default")
      (node (ref "LED10") (pin "9") (pinfunction "F_9") (pintype "bidirectional"))
      (node (ref "RA2") (pin "C2") (pinfunction "2_C2") (pintype "passive"))
    )
    (net (code "46") (name "Net-(LED10-G)") (class "Default")
      (node (ref "LED10") (pin "10") (pinfunction "G_10") (pintype "bidirectional"))
      (node (ref "RA2") (pin "D2") (pinfunction "2_D2") (pintype "passive"))
    )
    (net (code "47") (name "Net-(LED11-A)") (class "Default")
      (node (ref "LED11") (pin "7") (pinfunction "A_7") (pintype "bidirectional"))
      (node (ref "RA3") (pin "B2") (pinfunction "2_B2") (pintype "passive"))
    )
    (net (code "48") (name "Net-(LED11-B)") (class "Default")
      (node (ref "LED11") (pin "6") (pinfunction "B_6") (pintype "bidirectional"))
      (node (ref "RA3") (pin "A2") (pinfunction "2_A2") (pintype "passive"))
    )
    (net (code "49") (name "Net-(LED11-C)") (class "Default")
      (node (ref "LED11") (pin "4") (pinfunction "C_4") (pintype "bidirectional"))
      (node (ref "RA4") (pin "B2") (pinfunction "2_B2") (pintype "passive"))
    )
    (net (code "50") (name "Net-(LED11-D)") (class "Default")
      (node (ref "LED11") (pin "2") (pinfunction "D_2") (pintype "bidirectional"))
      (node (ref "RA4") (pin "C2") (pinfunction "2_C2") (pintype "passive"))
    )
    (net (code "51") (name "Net-(LED11-DP)") (class "Default")
      (node (ref "LED11") (pin "5") (pinfunction "DP_5") (pintype "bidirectional"))
      (node (ref "RA4") (pin "A2") (pinfunction "2_A2") (pintype "passive"))
    )
    (net (code "52") (name "Net-(LED11-E)") (class "Default")
      (node (ref "LED11") (pin "1") (pinfunction "E_1") (pintype "bidirectional"))
      (node (ref "RA4") (pin "D2") (pinfunction "2_D2") (pintype "passive"))
    )
    (net (code "53") (name "Net-(LED11-F)") (class "Default")
      (node (ref "LED11") (pin "9") (pinfunction "F_9") (pintype "bidirectional"))
      (node (ref "RA3") (pin "C2") (pinfunction "2_C2") (pintype "passive"))
    )
    (net (code "54") (name "Net-(LED11-G)") (class "Default")
      (node (ref "LED11") (pin "10") (pinfunction "G_10") (pintype "bidirectional"))
      (node (ref "RA3") (pin "D2") (pinfunction "2_D2") (pintype "passive"))
    )
    (net (code "55") (name "Net-(LED12-PadC)") (class "Default")
      (node (ref "LED12") (pin "C") (pinfunction "C_C") (pintype "passive"))
      (node (ref "R15") (pin "2") (pinfunction "2_2") (pintype "passive"))
    )
    (net (code "56") (name "Net-(LED13-PadC)") (class "Default")
      (node (ref "LED13") (pin "C") (pinfunction "C_C") (pintype "passive"))
      (node (ref "R16") (pin "2") (pinfunction "2_2") (pintype "passive"))
    )
    (net (code "57") (name "Net-(LED14-PadC)") (class "Default")
      (node (ref "LED14") (pin "C") (pinfunction "C_C") (pintype "passive"))
      (node (ref "R17") (pin "2") (pinfunction "2_2") (pintype "passive"))
    )
    (net (code "58") (name "Net-(RA1A-1)") (class "Default")
      (node (ref "RA1") (pin "A1") (pinfunction "1_A1") (pintype "passive"))
      (node (ref "U5") (pin "3") (pinfunction "QA_3") (pintype "bidirectional"))
    )
    (net (code "59") (name "Net-(RA1B-1)") (class "Default")
      (node (ref "RA1") (pin "B1") (pinfunction "1_B1") (pintype "passive"))
      (node (ref "U5") (pin "4") (pinfunction "QB_4") (pintype "bidirectional"))
    )
    (net (code "60") (name "Net-(RA1C-1)") (class "Default")
      (node (ref "RA1") (pin "C1") (pinfunction "1_C1") (pintype "passive"))
      (node (ref "U5") (pin "5") (pinfunction "QC_5") (pintype "bidirectional"))
    )
    (net (code "61") (name "Net-(RA1D-1)") (class "Default")
      (node (ref "RA1") (pin "D1") (pinfunction "1_D1") (pintype "passive"))
      (node (ref "U5") (pin "6") (pinfunction "QD_6") (pintype "bidirectional"))
    )
    (net (code "62") (name "Net-(RA2A-1)") (class "Default")
      (node (ref "RA2") (pin "A1") (pinfunction "1_A1") (pintype "passive"))
      (node (ref "U5") (pin "10") (pinfunction "QE_10") (pintype "bidirectional"))
    )
    (net (code "63") (name "Net-(RA2B-1)") (class "Default")
      (node (ref "RA2") (pin "B1") (pinfunction "1_B1") (pintype "passive"))
      (node (ref "U5") (pin "11") (pinfunction "QF_11") (pintype "bidirectional"))
    )
    (net (code "64") (name "Net-(RA2C-1)") (class "Default")
      (node (ref "RA2") (pin "C1") (pinfunction "1_C1") (pintype "passive"))
      (node (ref "U5") (pin "12") (pinfunction "QG_12") (pintype "bidirectional"))
    )
    (net (code "65") (name "Net-(RA2D-1)") (class "Default")
      (node (ref "RA2") (pin "D1") (pinfunction "1_D1") (pintype "passive"))
      (node (ref "U5") (pin "13") (pinfunction "QH_13") (pintype "bidirectional"))
      (node (ref "U6") (pin "1") (pinfunction "A_1") (pintype "bidirectional"))
    )
    (net (code "66") (name "Net-(RA3A-1)") (class "Default")
      (node (ref "RA3") (pin "A1") (pinfunction "1_A1") (pintype "passive"))
      (node (ref "U6") (pin "3") (pinfunction "QA_3") (pintype "bidirectional"))
    )
    (net (code "67") (name "Net-(RA3B-1)") (class "Default")
      (node (ref "RA3") (pin "B1") (pinfunction "1_B1") (pintype "passive"))
      (node (ref "U6") (pin "4") (pinfunction "QB_4") (pintype "bidirectional"))
    )
    (net (code "68") (name "Net-(RA3C-1)") (class "Default")
      (node (ref "RA3") (pin "C1") (pinfunction "1_C1") (pintype "passive"))
      (node (ref "U6") (pin "5") (pinfunction "QC_5") (pintype "bidirectional"))
    )
    (net (code "69") (name "Net-(RA3D-1)") (class "Default")
      (node (ref "RA3") (pin "D1") (pinfunction "1_D1") (pintype "passive"))
      (node (ref "U6") (pin "6") (pinfunction "QD_6") (pintype "bidirectional"))
    )
    (net (code "70") (name "Net-(RA4A-1)") (class "Default")
      (node (ref "RA4") (pin "A1") (pinfunction "1_A1") (pintype "passive"))
      (node (ref "U6") (pin "10") (pinfunction "QE_10") (pintype "bidirectional"))
    )
    (net (code "71") (name "Net-(RA4B-1)") (class "Default")
      (node (ref "RA4") (pin "B1") (pinfunction "1_B1") (pintype "passive"))
      (node (ref "U6") (pin "11") (pinfunction "QF_11") (pintype "bidirectional"))
    )
    (net (code "72") (name "Net-(RA4C-1)") (class "Default")
      (node (ref "RA4") (pin "C1") (pinfunction "1_C1") (pintype "passive"))
      (node (ref "U6") (pin "12") (pinfunction "QG_12") (pintype "bidirectional"))
    )
    (net (code "73") (name "Net-(RA4D-1)") (class "Default")
      (node (ref "RA4") (pin "D1") (pinfunction "1_D1") (pintype "passive"))
      (node (ref "U6") (pin "13") (pinfunction "QH_13") (pintype "bidirectional"))
    )
    (net (code "74") (name "Net-(RA5A-2)") (class "Default")
      (node (ref "LED1") (pin "C") (pinfunction "C_C") (pintype "passive"))
      (node (ref "RA5") (pin "A2") (pinfunction "2_A2") (pintype "passive"))
    )
    (net (code "75") (name "Net-(RA5B-2)") (class "Default")
      (node (ref "LED2") (pin "C") (pinfunction "C_C") (pintype "passive"))
      (node (ref "RA5") (pin "B2") (pinfunction "2_B2") (pintype "passive"))
    )
    (net (code "76") (name "Net-(RA5C-2)") (class "Default")
      (node (ref "LED3") (pin "C") (pinfunction "C_C") (pintype "passive"))
      (node (ref "RA5") (pin "C2") (pinfunction "2_C2") (pintype "passive"))
    )
    (net (code "77") (name "Net-(RA5D-2)") (class "Default")
      (node (ref "LED15") (pin "C") (pinfunction "C_C") (pintype "passive"))
      (node (ref "RA5") (pin "D2") (pinfunction "2_D2") (pintype "passive"))
    )
    (net (code "78") (name "Net-(RA6A-2)") (class "Default")
      (node (ref "LED4") (pin "C") (pinfunction "C_C") (pintype "passive"))
      (node (ref "RA6") (pin "A2") (pinfunction "2_A2") (pintype "passive"))
    )
    (net (code "79") (name "Net-(RA6B-2)") (class "Default")
      (node (ref "LED5") (pin "C") (pinfunction "C_C") (pintype "passive"))
      (node (ref "RA6") (pin "B2") (pinfunction "2_B2") (pintype "passive"))
    )
    (net (code "80") (name "Net-(RA6C-2)") (class "Default")
      (node (ref "LED6") (pin "C") (pinfunction "C_C") (pintype "passive"))
      (node (ref "RA6") (pin "C2") (pinfunction "2_C2") (pintype "passive"))
    )
    (net (code "81") (name "Net-(RA6D-2)") (class "Default")
      (node (ref "LED7") (pin "C") (pinfunction "C_C") (pintype "passive"))
      (node (ref "RA6") (pin "D2") (pinfunction "2_D2") (pintype "passive"))
    )
    (net (code "82") (name "Net-(RA7A-2)") (class "Default")
      (node (ref "LED8") (pin "C") (pinfunction "C_C") (pintype "passive"))
      (node (ref "RA7") (pin "A2") (pinfunction "2_A2") (pintype "passive"))
    )
    (net (code "83") (name "Net-(RA7B-2)") (class "Default")
      (node (ref "LED9") (pin "C") (pinfunction "C_C") (pintype "passive"))
      (node (ref "RA7") (pin "B2") (pinfunction "2_B2") (pintype "passive"))
    )
    (net (code "84") (name "Net-(RA7C-2)") (class "Default")
      (node (ref "LED16") (pin "C") (pinfunction "C_C") (pintype "passive"))
      (node (ref "RA7") (pin "C2") (pinfunction "2_C2") (pintype "passive"))
    )
    (net (code "85") (name "Net-(RA7D-2)") (class "Default")
      (node (ref "LED17") (pin "C") (pinfunction "C_C") (pintype "passive"))
      (node (ref "RA7") (pin "D2") (pinfunction "2_D2") (pintype "passive"))
    )
    (net (code "86") (name "Net-(U2-DM)") (class "Default")
      (node (ref "R3") (pin "2") (pinfunction "2_2") (pintype "passive"))
      (node (ref "U2") (pin "39") (pinfunction "DM_39") (pintype "bidirectional"))
    )
    (net (code "87") (name "Net-(U2-DP)") (class "Default")
      (node (ref "R2") (pin "2") (pinfunction "2_2") (pintype "passive"))
      (node (ref "U2") (pin "38") (pinfunction "DP_38") (pintype "bidirectional"))
    )
    (net (code "88") (name "Net-(U3-3V3OUT)") (class "Default")
      (node (ref "C21") (pin "1") (pinfunction "1_1") (pintype "passive"))
      (node (ref "U3") (pin "17") (pinfunction "3V3OUT_17") (pintype "bidirectional"))
      (node (ref "U3") (pin "4") (pinfunction "VCCIO_4") (pintype "bidirectional"))
    )
    (net (code "89") (name "Net-(U3-DM)") (class "Default")
      (node (ref "R19") (pin "2") (pinfunction "2_2") (pintype "passive"))
      (node (ref "U3") (pin "16") (pinfunction "DM_16") (pintype "bidirectional"))
    )
    (net (code "90") (name "Net-(U3-DP)") (class "Default")
      (node (ref "R20") (pin "2") (pinfunction "2_2") (pintype "passive"))
      (node (ref "U3") (pin "15") (pinfunction "DP_15") (pintype "bidirectional"))
    )
    (net (code "91") (name "Net-(U3-RXD)") (class "Default")
      (node (ref "R22") (pin "1") (pinfunction "1_1") (pintype "passive"))
      (node (ref "U3") (pin "5") (pinfunction "RXD_5") (pintype "bidirectional"))
    )
    (net (code "92") (name "Net-(U3-TXD)") (class "Default")
      (node (ref "R21") (pin "1") (pinfunction "1_1") (pintype "passive"))
      (node (ref "U3") (pin "1") (pinfunction "TXD_1") (pintype "bidirectional"))
    )
    (net (code "93") (name "SR_CLK") (class "Default")
      (node (ref "R8") (pin "2") (pinfunction "2_2") (pintype "passive"))
      (node (ref "U2") (pin "25") (pinfunction "PA13/PWM2/NMI/USART0-CLK_25") (pintype "bidirectional"))
      (node (ref "U4") (pin "8") (pinfunction "CK_8") (pintype "bidirectional"))
      (node (ref "U5") (pin "8") (pinfunction "CK_8") (pintype "bidirectional"))
      (node (ref "U6") (pin "8") (pinfunction "CK_8") (pintype "bidirectional"))
      (node (ref "U7") (pin "2") (pinfunction "CK_2") (pintype "bidirectional"))
      (node (ref "U8") (pin "2") (pinfunction "CK_2") (pintype "bidirectional"))
    )
    (net (code "94") (name "SR_DI1") (class "Default")
      (node (ref "U2") (pin "28") (pinfunction "PA16/PWM4/TC-CLK1/SPI0-NPCS0_28") (pintype "bidirectional"))
      (node (ref "U7") (pin "7") (pinfunction "~{QH}_7") (pintype "bidirectional"))
    )
    (net (code "95") (name "SR_DI2") (class "Default")
      (node (ref "U2") (pin "23") (pinfunction "PA12/XOUT32/PWM1/TC-B2/USART0-CTS_23") (pintype "bidirectional"))
      (node (ref "U8") (pin "9") (pinfunction "QH_9") (pintype "bidirectional"))
    )
    (net (code "96") (name "SR_DO") (class "Default")
      (node (ref "U2") (pin "27") (pinfunction "PA15/PWM4/USART2-CLK/SPI0-SCK_27") (pintype "bidirectional"))
      (node (ref "U4") (pin "1") (pinfunction "A_1") (pintype "bidirectional"))
    )
    (net (code "97") (name "SW1") (class "Default")
      (node (ref "R36") (pin "1") (pinfunction "1_1") (pintype "passive"))
      (node (ref "SW1") (pin "A2") (pinfunction "A2_A2") (pintype "passive"))
      (node (ref "U8") (pin "3") (pinfunction "E_3") (pintype "bidirectional"))
    )
    (net (code "98") (name "SW2") (class "Default")
      (node (ref "R37") (pin "1") (pinfunction "1_1") (pintype "passive"))
      (node (ref "SW2") (pin "A1") (pinfunction "A1_A1") (pintype "passive"))
      (node (ref "U8") (pin "4") (pinfunction "F_4") (pintype "bidirectional"))
    )
    (net (code "99") (name "SW3") (class "Default")
      (node (ref "R39") (pin "1") (pinfunction "1_1") (pintype "passive"))
      (node (ref "SW3") (pin "B2") (pinfunction "B2_B2") (pintype "passive"))
      (node (ref "U8") (pin "6") (pinfunction "H_6") (pintype "bidirectional"))
    )
    (net (code "100") (name "SW4") (class "Default")
      (node (ref "R38") (pin "1") (pinfunction "1_1") (pintype "passive"))
      (node (ref "SW4") (pin "A2") (pinfunction "A2_A2") (pintype "passive"))
      (node (ref "U8") (pin "5") (pinfunction "G_5") (pintype "bidirectional"))
    )
    (net (code "101") (name "SW5") (class "Default")
      (node (ref "SW5") (pin "B1") (pinfunction "B1_B1") (pintype "passive"))
      (node (ref "U2") (pin "46") (pinfunction "PA27/TC-B0/USB_VBOF/USART2-RXD_46") (pintype "bidirectional"))
    )
    (net (code "102") (name "SW6") (class "Default")
      (node (ref "R30") (pin "1") (pinfunction "1_1") (pintype "passive"))
      (node (ref "SW6") (pin "B2") (pinfunction "B2_B2") (pintype "passive"))
      (node (ref "U7") (pin "13") (pinfunction "C_13") (pintype "bidirectional"))
    )
    (net (code "103") (name "SW7") (class "Default")
      (node (ref "R34") (pin "1") (pinfunction "1_1") (pintype "passive"))
      (node (ref "SW7") (pin "A2") (pinfunction "A2_A2") (pintype "passive"))
      (node (ref "U7") (pin "5") (pinfunction "G_5") (pintype "bidirectional"))
    )
    (net (code "104") (name "SW8") (class "Default")
      (node (ref "R32") (pin "1") (pinfunction "1_1") (pintype "passive"))
      (node (ref "SW8") (pin "A2") (pinfunction "A2_A2") (pintype "passive"))
      (node (ref "U7") (pin "3") (pinfunction "E_3") (pintype "bidirectional"))
    )
    (net (code "105") (name "SW9") (class "Default")
      (node (ref "R35") (pin "1") (pinfunction "1_1") (pintype "passive"))
      (node (ref "SW9") (pin "B2") (pinfunction "B2_B2") (pintype "passive"))
      (node (ref "U7") (pin "6") (pinfunction "H_6") (pintype "bidirectional"))
    )
    (net (code "106") (name "SW10") (class "Default")
      (node (ref "R33") (pin "1") (pinfunction "1_1") (pintype "passive"))
      (node (ref "SW10") (pin "B2") (pinfunction "B2_B2") (pintype "passive"))
      (node (ref "U7") (pin "4") (pinfunction "F_4") (pintype "bidirectional"))
    )
    (net (code "107") (name "SW11") (class "Default")
      (node (ref "R29") (pin "1") (pinfunction "1_1") (pintype "passive"))
      (node (ref "SW11") (pin "B2") (pinfunction "B2_B2") (pintype "passive"))
      (node (ref "U7") (pin "12") (pinfunction "B_12") (pintype "bidirectional"))
    )
    (net (code "108") (name "SW12") (class "Default")
      (node (ref "R28") (pin "1") (pinfunction "1_1") (pintype "passive"))
      (node (ref "SW12") (pin "B2") (pinfunction "B2_B2") (pintype "passive"))
      (node (ref "U7") (pin "11") (pinfunction "A_11") (pintype "bidirectional"))
    )
    (net (code "109") (name "SW13") (class "Default")
      (node (ref "SW13") (pin "B1") (pinfunction "B1_B1") (pintype "passive"))
      (node (ref "U2") (pin "45") (pinfunction "PA26/TC-A0/USB_ID/USART2-TXD_45") (pintype "bidirectional"))
    )
    (net (code "110") (name "SW14") (class "Default")
      (node (ref "R31") (pin "1") (pinfunction "1_1") (pintype "passive"))
      (node (ref "SW14") (pin "B1") (pinfunction "B1_B1") (pintype "passive"))
      (node (ref "U7") (pin "14") (pinfunction "D_14") (pintype "bidirectional"))
    )
    (net (code "111") (name "VBUS") (class "Default")
      (node (ref "C2") (pin "1") (pinfunction "1_1") (pintype "passive"))
      (node (ref "C20") (pin "1") (pinfunction "1_1") (pintype "passive"))
      (node (ref "CN1") (pin "1") (pinfunction "VBUS_1") (pintype "passive"))
      (node (ref "D1") (pin "C") (pinfunction "C_C") (pintype "passive"))
      (node (ref "FB1") (pin "1") (pinfunction "1_1") (pintype "passive"))
      (node (ref "U3") (pin "20") (pinfunction "VCC_20") (pintype "bidirectional"))
    )
    (net (code "112") (name "X_ASSOC") (class "Default")
      (node (ref "CN3") (pin "15") (pinfunction "ASSOC/DIO5_15") (pintype "bidirectional"))
      (node (ref "LED13") (pin "A") (pinfunction "A_A") (pintype "passive"))
    )
    (net (code "113") (name "X_COMBTN") (class "Default")
      (node (ref "CN3") (pin "20") (pinfunction "COM_BTN/AD0/DIO0_20") (pintype "bidirectional"))
    )
    (net (code "114") (name "X_ON") (class "Default")
      (node (ref "CN3") (pin "13") (pinfunction "ON/~{SLEEP}_13") (pintype "bidirectional"))
      (node (ref "LED12") (pin "A") (pinfunction "A_A") (pintype "passive"))
    )
    (net (code "115") (name "X_RSSI") (class "Default")
      (node (ref "CN3") (pin "6") (pinfunction "RSSI/PWM/DIO10_6") (pintype "bidirectional"))
      (node (ref "LED14") (pin "A") (pinfunction "A_A") (pintype "passive"))
    )
    (net (code "116") (name "X_RX") (class "Default")
      (node (ref "CN3") (pin "2") (pinfunction "DOUT_2") (pintype "bidirectional"))
      (node (ref "U2") (pin "43") (pinfunction "PA24/INT4/USART1-RXD/SPI0-NPCS0_43") (pintype "bidirectional"))
    )
    (net (code "117") (name "X_TX") (class "Default")
      (node (ref "CN3") (pin "3") (pinfunction "DIN/~{CONFIG}_3") (pintype "bidirectional"))
      (node (ref "U2") (pin "35") (pinfunction "PA23/INT3/USART1-TXD/SPI0-NPCS1_35") (pintype "bidirectional"))
    )
    (net (code "118") (name "unconnected-(CN1-ID-Pad4)") (class "Default")
      (node (ref "CN1") (pin "4") (pinfunction "ID_4") (pintype "passive"))
    )
    (net (code "119") (name "unconnected-(CN1-PadS2)") (class "Default")
      (node (ref "CN1") (pin "S2") (pinfunction "S2_S2") (pintype "passive"))
    )
    (net (code "120") (name "unconnected-(CN1-PadS3)") (class "Default")
      (node (ref "CN1") (pin "S3") (pinfunction "S3_S3") (pintype "passive"))
    )
    (net (code "121") (name "unconnected-(CN1-PadS4)") (class "Default")
      (node (ref "CN1") (pin "S4") (pinfunction "S4_S4") (pintype "passive"))
    )
    (net (code "122") (name "unconnected-(CN2-ID-Pad4)") (class "Default")
      (node (ref "CN2") (pin "4") (pinfunction "ID_4") (pintype "passive"))
    )
    (net (code "123") (name "unconnected-(CN2-PadS1)") (class "Default")
      (node (ref "CN2") (pin "S1") (pinfunction "S1_S1") (pintype "passive"))
    )
    (net (code "124") (name "unconnected-(CN2-PadS2)") (class "Default")
      (node (ref "CN2") (pin "S2") (pinfunction "S2_S2") (pintype "passive"))
    )
    (net (code "125") (name "unconnected-(CN2-PadS4)") (class "Default")
      (node (ref "CN2") (pin "S4") (pinfunction "S4_S4") (pintype "passive"))
    )
    (net (code "126") (name "unconnected-(CN3-AD1{slash}DIO1-Pad19)") (class "Default")
      (node (ref "CN3") (pin "19") (pinfunction "AD1/DIO1_19") (pintype "bidirectional"))
    )
    (net (code "127") (name "unconnected-(CN3-AD2{slash}DIO2-Pad18)") (class "Default")
      (node (ref "CN3") (pin "18") (pinfunction "AD2/DIO2_18") (pintype "bidirectional"))
    )
    (net (code "128") (name "unconnected-(CN3-AD3{slash}DIO3-Pad17)") (class "Default")
      (node (ref "CN3") (pin "17") (pinfunction "AD3/DIO3_17") (pintype "bidirectional"))
    )
    (net (code "129") (name "unconnected-(CN3-DIO4-Pad11)") (class "Default")
      (node (ref "CN3") (pin "11") (pinfunction "DIO4_11") (pintype "bidirectional"))
    )
    (net (code "130") (name "unconnected-(CN3-DIO11-Pad7)") (class "Default")
      (node (ref "CN3") (pin "7") (pinfunction "DIO11_7") (pintype "bidirectional"))
    )
    (net (code "131") (name "unconnected-(CN3-DIO12-Pad4)") (class "Default")
      (node (ref "CN3") (pin "4") (pinfunction "DIO12_4") (pintype "bidirectional"))
    )
    (net (code "132") (name "unconnected-(CN3-RSVD-Pad8)") (class "Default")
      (node (ref "CN3") (pin "8") (pinfunction "RSVD_8") (pintype "bidirectional"))
    )
    (net (code "133") (name "unconnected-(SW0-PadB2)") (class "Default")
      (node (ref "SW0") (pin "B2") (pinfunction "B2_B2") (pintype "passive"))
    )
    (net (code "134") (name "unconnected-(SW1-PadA1)") (class "Default")
      (node (ref "SW1") (pin "A1") (pinfunction "A1_A1") (pintype "passive"))
    )
    (net (code "135") (name "unconnected-(SW2-PadA2)") (class "Default")
      (node (ref "SW2") (pin "A2") (pinfunction "A2_A2") (pintype "passive"))
    )
    (net (code "136") (name "unconnected-(SW3-PadB1)") (class "Default")
      (node (ref "SW3") (pin "B1") (pinfunction "B1_B1") (pintype "passive"))
    )
    (net (code "137") (name "unconnected-(SW4-PadA1)") (class "Default")
      (node (ref "SW4") (pin "A1") (pinfunction "A1_A1") (pintype "passive"))
    )
    (net (code "138") (name "unconnected-(SW5-PadB2)") (class "Default")
      (node (ref "SW5") (pin "B2") (pinfunction "B2_B2") (pintype "passive"))
    )
    (net (code "139") (name "unconnected-(SW6-PadB1)") (class "Default")
      (node (ref "SW6") (pin "B1") (pinfunction "B1_B1") (pintype "passive"))
    )
    (net (code "140") (name "unconnected-(SW7-PadA1)") (class "Default")
      (node (ref "SW7") (pin "A1") (pinfunction "A1_A1") (pintype "passive"))
    )
    (net (code "141") (name "unconnected-(SW8-PadA1)") (class "Default")
      (node (ref "SW8") (pin "A1") (pinfunction "A1_A1") (pintype "passive"))
    )
    (net (code "142") (name "unconnected-(SW9-PadB1)") (class "Default")
      (node (ref "SW9") (pin "B1") (pinfunction "B1_B1") (pintype "passive"))
    )
    (net (code "143") (name "unconnected-(SW10-PadB1)") (class "Default")
      (node (ref "SW10") (pin "B1") (pinfunction "B1_B1") (pintype "passive"))
    )
    (net (code "144") (name "unconnected-(SW11-PadB1)") (class "Default")
      (node (ref "SW11") (pin "B1") (pinfunction "B1_B1") (pintype "passive"))
    )
    (net (code "145") (name "unconnected-(SW12-PadB1)") (class "Default")
      (node (ref "SW12") (pin "B1") (pinfunction "B1_B1") (pintype "passive"))
    )
    (net (code "146") (name "unconnected-(SW13-PadB2)") (class "Default")
      (node (ref "SW13") (pin "B2") (pinfunction "B2_B2") (pintype "passive"))
    )
    (net (code "147") (name "unconnected-(SW14-PadB2)") (class "Default")
      (node (ref "SW14") (pin "B2") (pinfunction "B2_B2") (pintype "passive"))
    )
    (net (code "148") (name "unconnected-(U2-PA07{slash}AD4{slash}PWM0{slash}USART1-DTR-Pad11)") (class "Default")
      (node (ref "U2") (pin "11") (pinfunction "PA07/AD4/PWM0/USART1-DTR_11") (pintype "bidirectional"))
    )
    (net (code "149") (name "unconnected-(U2-PA08{slash}AD5{slash}PWM1{slash}USART1-RI-Pad12)") (class "Default")
      (node (ref "U2") (pin "12") (pinfunction "PA08/AD5/PWM1/USART1-RI_12") (pintype "bidirectional"))
    )
    (net (code "150") (name "unconnected-(U2-PA11{slash}XIN32{slash}PWM0{slash}TC-A2{slash}USART0-RTS-Pad22)") (class "Default")
      (node (ref "U2") (pin "22") (pinfunction "PA11/XIN32/PWM0/TC-A2/USART0-RTS_22") (pintype "bidirectional"))
    )
    (net (code "151") (name "unconnected-(U2-PA19{slash}XOUT0{slash}PWM6{slash}USART0-TXD{slash}SPI0-MOSI-Pad31)") (class "Default")
      (node (ref "U2") (pin "31") (pinfunction "PA19/XOUT0/PWM6/USART0-TXD/SPI0-MOSI_31") (pintype "bidirectional"))
    )
    (net (code "152") (name "unconnected-(U2-PA25{slash}INT5{slash}PWM3{slash}SPI0-MISO-Pad44)") (class "Default")
      (node (ref "U2") (pin "44") (pinfunction "PA25/INT5/PWM3/SPI0-MISO_44") (pintype "bidirectional"))
    )
    (net (code "153") (name "unconnected-(U3-CBUS0-Pad23)") (class "Default")
      (node (ref "U3") (pin "23") (pinfunction "CBUS0_23") (pintype "bidirectional"))
    )
    (net (code "154") (name "unconnected-(U3-CBUS1-Pad22)") (class "Default")
      (node (ref "U3") (pin "22") (pinfunction "CBUS1_22") (pintype "bidirectional"))
    )
    (net (code "155") (name "unconnected-(U3-CBUS2-Pad13)") (class "Default")
      (node (ref "U3") (pin "13") (pinfunction "CBUS2_13") (pintype "bidirectional"))
    )
    (net (code "156") (name "unconnected-(U3-CBUS3-Pad14)") (class "Default")
      (node (ref "U3") (pin "14") (pinfunction "CBUS3_14") (pintype "bidirectional"))
    )
    (net (code "157") (name "unconnected-(U3-CBUS4-Pad12)") (class "Default")
      (node (ref "U3") (pin "12") (pinfunction "CBUS4_12") (pintype "bidirectional"))
    )
    (net (code "158") (name "unconnected-(U3-OSCI-Pad27)") (class "Default")
      (node (ref "U3") (pin "27") (pinfunction "OSCI_27") (pintype "bidirectional"))
    )
    (net (code "159") (name "unconnected-(U3-OSCO-Pad28)") (class "Default")
      (node (ref "U3") (pin "28") (pinfunction "OSCO_28") (pintype "bidirectional"))
    )
    (net (code "160") (name "unconnected-(U3-~{CTS}-Pad11)") (class "Default")
      (node (ref "U3") (pin "11") (pinfunction "~{CTS}_11") (pintype "bidirectional"))
    )
    (net (code "161") (name "unconnected-(U3-~{DCD}-Pad10)") (class "Default")
      (node (ref "U3") (pin "10") (pinfunction "~{DCD}_10") (pintype "bidirectional"))
    )
    (net (code "162") (name "unconnected-(U3-~{DSR}-Pad9)") (class "Default")
      (node (ref "U3") (pin "9") (pinfunction "~{DSR}_9") (pintype "bidirectional"))
    )
    (net (code "163") (name "unconnected-(U3-~{DTR}-Pad2)") (class "Default")
      (node (ref "U3") (pin "2") (pinfunction "~{DTR}_2") (pintype "bidirectional"))
    )
    (net (code "164") (name "unconnected-(U3-~{RESET}-Pad19)") (class "Default")
      (node (ref "U3") (pin "19") (pinfunction "~{RESET}_19") (pintype "bidirectional"))
    )
    (net (code "165") (name "unconnected-(U3-~{RI}-Pad6)") (class "Default")
      (node (ref "U3") (pin "6") (pinfunction "~{RI}_6") (pintype "bidirectional"))
    )
    (net (code "166") (name "unconnected-(U3-~{RTS}-Pad3)") (class "Default")
      (node (ref "U3") (pin "3") (pinfunction "~{RTS}_3") (pintype "bidirectional"))
    )
    (net (code "167") (name "unconnected-(U7-QH-Pad9)") (class "Default")
      (node (ref "U7") (pin "9") (pinfunction "QH_9") (pintype "bidirectional"))
    )
    (net (code "168") (name "unconnected-(U8-A-Pad11)") (class "Default")
      (node (ref "U8") (pin "11") (pinfunction "A_11") (pintype "bidirectional"))
    )
    (net (code "169") (name "unconnected-(U8-B-Pad12)") (class "Default")
      (node (ref "U8") (pin "12") (pinfunction "B_12") (pintype "bidirectional"))
    )
    (net (code "170") (name "unconnected-(U8-C-Pad13)") (class "Default")
      (node (ref "U8") (pin "13") (pinfunction "C_13") (pintype "bidirectional"))
    )
    (net (code "171") (name "unconnected-(U8-D-Pad14)") (class "Default")
      (node (ref "U8") (pin "14") (pinfunction "D_14") (pintype "bidirectional"))
    )
    (net (code "172") (name "unconnected-(U8-~{QH}-Pad7)") (class "Default")
      (node (ref "U8") (pin "7") (pinfunction "~{QH}_7") (pintype "bidirectional"))
    )
  )
)
